# W603X.net
KiCad netlist of a schematic drawn in EAGLE
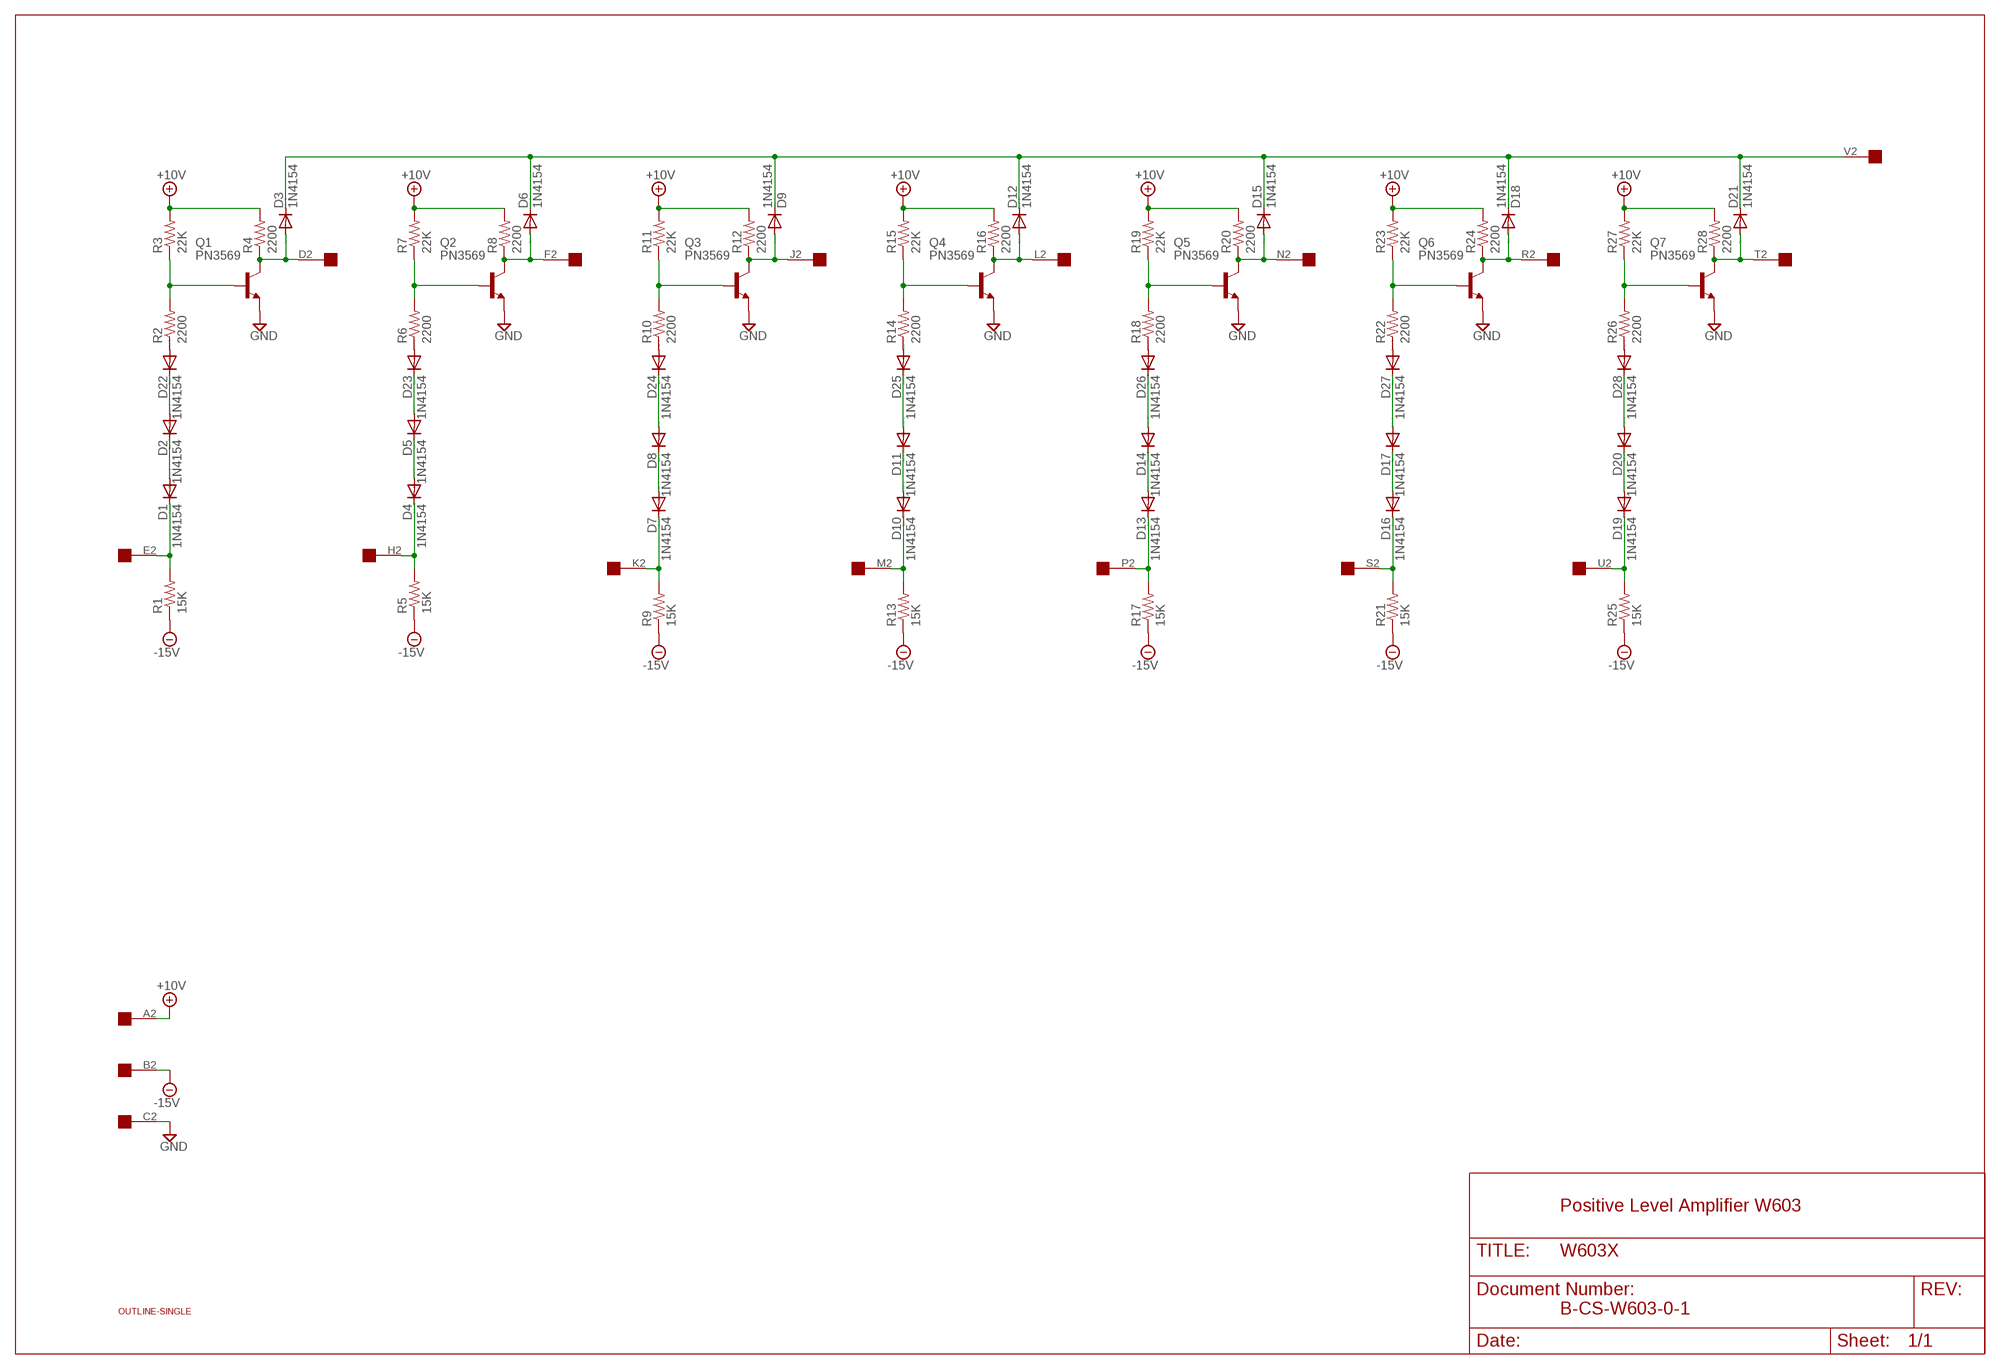
[diagram p0: schematic, sheet 1]

(export (version "E")
  (design (tool "Eeschema 10.0.6"))
  (components
    (comp (ref "D1")
      (value "1N4154")
      (footprint "eagle-import:DO35-10")
      (libsource (lib "eagle-import") (part "1N4148DO35-10"))
    )
    (comp (ref "D2")
      (value "1N4154")
      (footprint "eagle-import:DO35-10")
      (libsource (lib "eagle-import") (part "1N4148DO35-10"))
    )
    (comp (ref "D3")
      (value "1N4154")
      (footprint "eagle-import:DO35-10")
      (libsource (lib "eagle-import") (part "1N4148DO35-10"))
    )
    (comp (ref "D4")
      (value "1N4154")
      (footprint "eagle-import:DO35-10")
      (libsource (lib "eagle-import") (part "1N4148DO35-10"))
    )
    (comp (ref "D5")
      (value "1N4154")
      (footprint "eagle-import:DO35-10")
      (libsource (lib "eagle-import") (part "1N4148DO35-10"))
    )
    (comp (ref "D6")
      (value "1N4154")
      (footprint "eagle-import:DO35-10")
      (libsource (lib "eagle-import") (part "1N4148DO35-10"))
    )
    (comp (ref "D7")
      (value "1N4154")
      (footprint "eagle-import:DO35-10")
      (libsource (lib "eagle-import") (part "1N4148DO35-10"))
    )
    (comp (ref "D8")
      (value "1N4154")
      (footprint "eagle-import:DO35-10")
      (libsource (lib "eagle-import") (part "1N4148DO35-10"))
    )
    (comp (ref "D9")
      (value "1N4154")
      (footprint "eagle-import:DO35-10")
      (libsource (lib "eagle-import") (part "1N4148DO35-10"))
    )
    (comp (ref "D10")
      (value "1N4154")
      (footprint "eagle-import:DO35-10")
      (libsource (lib "eagle-import") (part "1N4148DO35-10"))
    )
    (comp (ref "D11")
      (value "1N4154")
      (footprint "eagle-import:DO35-10")
      (libsource (lib "eagle-import") (part "1N4148DO35-10"))
    )
    (comp (ref "D12")
      (value "1N4154")
      (footprint "eagle-import:DO35-10")
      (libsource (lib "eagle-import") (part "1N4148DO35-10"))
    )
    (comp (ref "D13")
      (value "1N4154")
      (footprint "eagle-import:DO35-10")
      (libsource (lib "eagle-import") (part "1N4148DO35-10"))
    )
    (comp (ref "D14")
      (value "1N4154")
      (footprint "eagle-import:DO35-10")
      (libsource (lib "eagle-import") (part "1N4148DO35-10"))
    )
    (comp (ref "D15")
      (value "1N4154")
      (footprint "eagle-import:DO35-10")
      (libsource (lib "eagle-import") (part "1N4148DO35-10"))
    )
    (comp (ref "D16")
      (value "1N4154")
      (footprint "eagle-import:DO35-10")
      (libsource (lib "eagle-import") (part "1N4148DO35-10"))
    )
    (comp (ref "D17")
      (value "1N4154")
      (footprint "eagle-import:DO35-10")
      (libsource (lib "eagle-import") (part "1N4148DO35-10"))
    )
    (comp (ref "D18")
      (value "1N4154")
      (footprint "eagle-import:DO35-10")
      (libsource (lib "eagle-import") (part "1N4148DO35-10"))
    )
    (comp (ref "D19")
      (value "1N4154")
      (footprint "eagle-import:DO35-10")
      (libsource (lib "eagle-import") (part "1N4148DO35-10"))
    )
    (comp (ref "D20")
      (value "1N4154")
      (footprint "eagle-import:DO35-10")
      (libsource (lib "eagle-import") (part "1N4148DO35-10"))
    )
    (comp (ref "D21")
      (value "1N4154")
      (footprint "eagle-import:DO35-10")
      (libsource (lib "eagle-import") (part "1N4148DO35-10"))
    )
    (comp (ref "D22")
      (value "1N4154")
      (footprint "eagle-import:DO35-10")
      (libsource (lib "eagle-import") (part "1N4148DO35-10"))
    )
    (comp (ref "D23")
      (value "1N4154")
      (footprint "eagle-import:DO35-10")
      (libsource (lib "eagle-import") (part "1N4148DO35-10"))
    )
    (comp (ref "D24")
      (value "1N4154")
      (footprint "eagle-import:DO35-10")
      (libsource (lib "eagle-import") (part "1N4148DO35-10"))
    )
    (comp (ref "D25")
      (value "1N4154")
      (footprint "eagle-import:DO35-10")
      (libsource (lib "eagle-import") (part "1N4148DO35-10"))
    )
    (comp (ref "D26")
      (value "1N4154")
      (footprint "eagle-import:DO35-10")
      (libsource (lib "eagle-import") (part "1N4148DO35-10"))
    )
    (comp (ref "D27")
      (value "1N4154")
      (footprint "eagle-import:DO35-10")
      (libsource (lib "eagle-import") (part "1N4148DO35-10"))
    )
    (comp (ref "D28")
      (value "1N4154")
      (footprint "eagle-import:DO35-10")
      (libsource (lib "eagle-import") (part "1N4148DO35-10"))
    )
    (comp (ref "Q1")
      (value "PN3569")
      (footprint "eagle-import:TO5")
      (libsource (lib "eagle-import") (part "2N2102"))
    )
    (comp (ref "Q2")
      (value "PN3569")
      (footprint "eagle-import:TO5")
      (libsource (lib "eagle-import") (part "2N2102"))
    )
    (comp (ref "Q3")
      (value "PN3569")
      (footprint "eagle-import:TO5")
      (libsource (lib "eagle-import") (part "2N2102"))
    )
    (comp (ref "Q4")
      (value "PN3569")
      (footprint "eagle-import:TO5")
      (libsource (lib "eagle-import") (part "2N2102"))
    )
    (comp (ref "Q5")
      (value "PN3569")
      (footprint "eagle-import:TO5")
      (libsource (lib "eagle-import") (part "2N2102"))
    )
    (comp (ref "Q6")
      (value "PN3569")
      (footprint "eagle-import:TO5")
      (libsource (lib "eagle-import") (part "2N2102"))
    )
    (comp (ref "Q7")
      (value "PN3569")
      (footprint "eagle-import:TO5")
      (libsource (lib "eagle-import") (part "2N2102"))
    )
    (comp (ref "R1")
      (value "15K")
      (footprint "eagle-import:0207_10")
      (libsource (lib "eagle-import") (part "R-US_0207/10"))
    )
    (comp (ref "R2")
      (value "2200")
      (footprint "eagle-import:0207_10")
      (libsource (lib "eagle-import") (part "R-US_0207/10"))
    )
    (comp (ref "R3")
      (value "22K")
      (footprint "eagle-import:0207_10")
      (libsource (lib "eagle-import") (part "R-US_0207/10"))
    )
    (comp (ref "R4")
      (value "2200")
      (footprint "eagle-import:0207_10")
      (libsource (lib "eagle-import") (part "R-US_0207/10"))
    )
    (comp (ref "R5")
      (value "15K")
      (footprint "eagle-import:0207_10")
      (libsource (lib "eagle-import") (part "R-US_0207/10"))
    )
    (comp (ref "R6")
      (value "2200")
      (footprint "eagle-import:0207_10")
      (libsource (lib "eagle-import") (part "R-US_0207/10"))
    )
    (comp (ref "R7")
      (value "22K")
      (footprint "eagle-import:0207_10")
      (libsource (lib "eagle-import") (part "R-US_0207/10"))
    )
    (comp (ref "R8")
      (value "2200")
      (footprint "eagle-import:0207_10")
      (libsource (lib "eagle-import") (part "R-US_0207/10"))
    )
    (comp (ref "R9")
      (value "15K")
      (footprint "eagle-import:0207_10")
      (libsource (lib "eagle-import") (part "R-US_0207/10"))
    )
    (comp (ref "R10")
      (value "2200")
      (footprint "eagle-import:0207_10")
      (libsource (lib "eagle-import") (part "R-US_0207/10"))
    )
    (comp (ref "R11")
      (value "22K")
      (footprint "eagle-import:0207_10")
      (libsource (lib "eagle-import") (part "R-US_0207/10"))
    )
    (comp (ref "R12")
      (value "2200")
      (footprint "eagle-import:0207_10")
      (libsource (lib "eagle-import") (part "R-US_0207/10"))
    )
    (comp (ref "R13")
      (value "15K")
      (footprint "eagle-import:0207_10")
      (libsource (lib "eagle-import") (part "R-US_0207/10"))
    )
    (comp (ref "R14")
      (value "2200")
      (footprint "eagle-import:0207_10")
      (libsource (lib "eagle-import") (part "R-US_0207/10"))
    )
    (comp (ref "R15")
      (value "22K")
      (footprint "eagle-import:0207_10")
      (libsource (lib "eagle-import") (part "R-US_0207/10"))
    )
    (comp (ref "R16")
      (value "2200")
      (footprint "eagle-import:0207_10")
      (libsource (lib "eagle-import") (part "R-US_0207/10"))
    )
    (comp (ref "R17")
      (value "15K")
      (footprint "eagle-import:0207_10")
      (libsource (lib "eagle-import") (part "R-US_0207/10"))
    )
    (comp (ref "R18")
      (value "2200")
      (footprint "eagle-import:0207_10")
      (libsource (lib "eagle-import") (part "R-US_0207/10"))
    )
    (comp (ref "R19")
      (value "22K")
      (footprint "eagle-import:0207_10")
      (libsource (lib "eagle-import") (part "R-US_0207/10"))
    )
    (comp (ref "R20")
      (value "2200")
      (footprint "eagle-import:0207_10")
      (libsource (lib "eagle-import") (part "R-US_0207/10"))
    )
    (comp (ref "R21")
      (value "15K")
      (footprint "eagle-import:0207_10")
      (libsource (lib "eagle-import") (part "R-US_0207/10"))
    )
    (comp (ref "R22")
      (value "2200")
      (footprint "eagle-import:0207_10")
      (libsource (lib "eagle-import") (part "R-US_0207/10"))
    )
    (comp (ref "R23")
      (value "22K")
      (footprint "eagle-import:0207_10")
      (libsource (lib "eagle-import") (part "R-US_0207/10"))
    )
    (comp (ref "R24")
      (value "2200")
      (footprint "eagle-import:0207_10")
      (libsource (lib "eagle-import") (part "R-US_0207/10"))
    )
    (comp (ref "R25")
      (value "15K")
      (footprint "eagle-import:0207_10")
      (libsource (lib "eagle-import") (part "R-US_0207/10"))
    )
    (comp (ref "R26")
      (value "2200")
      (footprint "eagle-import:0207_10")
      (libsource (lib "eagle-import") (part "R-US_0207/10"))
    )
    (comp (ref "R27")
      (value "22K")
      (footprint "eagle-import:0207_10")
      (libsource (lib "eagle-import") (part "R-US_0207/10"))
    )
    (comp (ref "R28")
      (value "2200")
      (footprint "eagle-import:0207_10")
      (libsource (lib "eagle-import") (part "R-US_0207/10"))
    )
    (comp (ref "U$1")
      (value "OUTLINE-SINGLE")
      (footprint "eagle-import:SINGLE")
      (libsource (lib "eagle-import") (part "OUTLINE-SINGLE"))
    )
    (comp (ref "U$2")
      (value "EDGE-1")
      (footprint "eagle-import:EDGE-CON1")
      (libsource (lib "eagle-import") (part "EDGE-1"))
    )
  )
  (nets
    (net (code "1") (name "+10V") (class "Default")
      (node (ref "R11") (pin "2") (pinfunction "2_2") (pintype "passive"))
      (node (ref "R12") (pin "2") (pinfunction "2_2") (pintype "passive"))
      (node (ref "R15") (pin "2") (pinfunction "2_2") (pintype "passive"))
      (node (ref "R16") (pin "2") (pinfunction "2_2") (pintype "passive"))
      (node (ref "R19") (pin "2") (pinfunction "2_2") (pintype "passive"))
      (node (ref "R20") (pin "2") (pinfunction "2_2") (pintype "passive"))
      (node (ref "R23") (pin "2") (pinfunction "2_2") (pintype "passive"))
      (node (ref "R24") (pin "2") (pinfunction "2_2") (pintype "passive"))
      (node (ref "R27") (pin "2") (pinfunction "2_2") (pintype "passive"))
      (node (ref "R28") (pin "2") (pinfunction "2_2") (pintype "passive"))
      (node (ref "R3") (pin "2") (pinfunction "2_2") (pintype "passive"))
      (node (ref "R4") (pin "2") (pinfunction "2_2") (pintype "passive"))
      (node (ref "R7") (pin "2") (pinfunction "2_2") (pintype "passive"))
      (node (ref "R8") (pin "2") (pinfunction "2_2") (pintype "passive"))
      (node (ref "U$2") (pin "A2") (pinfunction "1_A2") (pintype "bidirectional"))
    )
    (net (code "2") (name "-15V") (class "Default")
      (node (ref "R1") (pin "1") (pinfunction "1_1") (pintype "passive"))
      (node (ref "R13") (pin "1") (pinfunction "1_1") (pintype "passive"))
      (node (ref "R17") (pin "1") (pinfunction "1_1") (pintype "passive"))
      (node (ref "R21") (pin "1") (pinfunction "1_1") (pintype "passive"))
      (node (ref "R25") (pin "1") (pinfunction "1_1") (pintype "passive"))
      (node (ref "R5") (pin "1") (pinfunction "1_1") (pintype "passive"))
      (node (ref "R9") (pin "1") (pinfunction "1_1") (pintype "passive"))
      (node (ref "U$2") (pin "B2") (pinfunction "1_B2") (pintype "bidirectional"))
    )
    (net (code "3") (name "GND") (class "Default")
      (node (ref "Q1") (pin "1") (pinfunction "E_1") (pintype "passive"))
      (node (ref "Q2") (pin "1") (pinfunction "E_1") (pintype "passive"))
      (node (ref "Q3") (pin "1") (pinfunction "E_1") (pintype "passive"))
      (node (ref "Q4") (pin "1") (pinfunction "E_1") (pintype "passive"))
      (node (ref "Q5") (pin "1") (pinfunction "E_1") (pintype "passive"))
      (node (ref "Q6") (pin "1") (pinfunction "E_1") (pintype "passive"))
      (node (ref "Q7") (pin "1") (pinfunction "E_1") (pintype "passive"))
      (node (ref "U$2") (pin "C2") (pinfunction "1_C2") (pintype "bidirectional"))
    )
    (net (code "4") (name "Net-(D1-PadA)") (class "Default")
      (node (ref "D1") (pin "A") (pinfunction "A_A") (pintype "passive"))
      (node (ref "D2") (pin "C") (pinfunction "C_C") (pintype "passive"))
    )
    (net (code "5") (name "Net-(D2-PadA)") (class "Default")
      (node (ref "D2") (pin "A") (pinfunction "A_A") (pintype "passive"))
      (node (ref "D22") (pin "C") (pinfunction "C_C") (pintype "passive"))
    )
    (net (code "6") (name "Net-(D4-PadA)") (class "Default")
      (node (ref "D4") (pin "A") (pinfunction "A_A") (pintype "passive"))
      (node (ref "D5") (pin "C") (pinfunction "C_C") (pintype "passive"))
    )
    (net (code "7") (name "Net-(D7-PadA)") (class "Default")
      (node (ref "D7") (pin "A") (pinfunction "A_A") (pintype "passive"))
      (node (ref "D8") (pin "C") (pinfunction "C_C") (pintype "passive"))
    )
    (net (code "8") (name "Net-(D10-PadA)") (class "Default")
      (node (ref "D10") (pin "A") (pinfunction "A_A") (pintype "passive"))
      (node (ref "D11") (pin "C") (pinfunction "C_C") (pintype "passive"))
    )
    (net (code "9") (name "Net-(D11-PadA)") (class "Default")
      (node (ref "D11") (pin "A") (pinfunction "A_A") (pintype "passive"))
      (node (ref "D25") (pin "C") (pinfunction "C_C") (pintype "passive"))
    )
    (net (code "10") (name "Net-(D13-PadA)") (class "Default")
      (node (ref "D13") (pin "A") (pinfunction "A_A") (pintype "passive"))
      (node (ref "D14") (pin "C") (pinfunction "C_C") (pintype "passive"))
    )
    (net (code "11") (name "Net-(D14-PadA)") (class "Default")
      (node (ref "D14") (pin "A") (pinfunction "A_A") (pintype "passive"))
      (node (ref "D26") (pin "C") (pinfunction "C_C") (pintype "passive"))
    )
    (net (code "12") (name "Net-(D16-PadA)") (class "Default")
      (node (ref "D16") (pin "A") (pinfunction "A_A") (pintype "passive"))
      (node (ref "D17") (pin "C") (pinfunction "C_C") (pintype "passive"))
    )
    (net (code "13") (name "Net-(D17-PadA)") (class "Default")
      (node (ref "D17") (pin "A") (pinfunction "A_A") (pintype "passive"))
      (node (ref "D27") (pin "C") (pinfunction "C_C") (pintype "passive"))
    )
    (net (code "14") (name "Net-(D19-PadA)") (class "Default")
      (node (ref "D19") (pin "A") (pinfunction "A_A") (pintype "passive"))
      (node (ref "D20") (pin "C") (pinfunction "C_C") (pintype "passive"))
    )
    (net (code "15") (name "Net-(D20-PadA)") (class "Default")
      (node (ref "D20") (pin "A") (pinfunction "A_A") (pintype "passive"))
      (node (ref "D28") (pin "C") (pinfunction "C_C") (pintype "passive"))
    )
    (net (code "16") (name "Net-(D22-PadA)") (class "Default")
      (node (ref "D22") (pin "A") (pinfunction "A_A") (pintype "passive"))
      (node (ref "R2") (pin "1") (pinfunction "1_1") (pintype "passive"))
    )
    (net (code "17") (name "Net-(D23-PadA)") (class "Default")
      (node (ref "D23") (pin "A") (pinfunction "A_A") (pintype "passive"))
      (node (ref "R6") (pin "1") (pinfunction "1_1") (pintype "passive"))
    )
    (net (code "18") (name "Net-(D23-PadC)") (class "Default")
      (node (ref "D23") (pin "C") (pinfunction "C_C") (pintype "passive"))
      (node (ref "D5") (pin "A") (pinfunction "A_A") (pintype "passive"))
    )
    (net (code "19") (name "Net-(D24-PadA)") (class "Default")
      (node (ref "D24") (pin "A") (pinfunction "A_A") (pintype "passive"))
      (node (ref "R10") (pin "1") (pinfunction "1_1") (pintype "passive"))
    )
    (net (code "20") (name "Net-(D24-PadC)") (class "Default")
      (node (ref "D24") (pin "C") (pinfunction "C_C") (pintype "passive"))
      (node (ref "D8") (pin "A") (pinfunction "A_A") (pintype "passive"))
    )
    (net (code "21") (name "Net-(D25-PadA)") (class "Default")
      (node (ref "D25") (pin "A") (pinfunction "A_A") (pintype "passive"))
      (node (ref "R14") (pin "1") (pinfunction "1_1") (pintype "passive"))
    )
    (net (code "22") (name "Net-(D26-PadA)") (class "Default")
      (node (ref "D26") (pin "A") (pinfunction "A_A") (pintype "passive"))
      (node (ref "R18") (pin "1") (pinfunction "1_1") (pintype "passive"))
    )
    (net (code "23") (name "Net-(D27-PadA)") (class "Default")
      (node (ref "D27") (pin "A") (pinfunction "A_A") (pintype "passive"))
      (node (ref "R22") (pin "1") (pinfunction "1_1") (pintype "passive"))
    )
    (net (code "24") (name "Net-(D28-PadA)") (class "Default")
      (node (ref "D28") (pin "A") (pinfunction "A_A") (pintype "passive"))
      (node (ref "R26") (pin "1") (pinfunction "1_1") (pintype "passive"))
    )
    (net (code "25") (name "Net-(Q1-B)") (class "Default")
      (node (ref "Q1") (pin "2") (pinfunction "B_2") (pintype "passive"))
      (node (ref "R2") (pin "2") (pinfunction "2_2") (pintype "passive"))
      (node (ref "R3") (pin "1") (pinfunction "1_1") (pintype "passive"))
    )
    (net (code "26") (name "Net-(Q1-C)") (class "Default")
      (node (ref "D3") (pin "A") (pinfunction "A_A") (pintype "passive"))
      (node (ref "Q1") (pin "3") (pinfunction "C_3") (pintype "passive"))
      (node (ref "R4") (pin "1") (pinfunction "1_1") (pintype "passive"))
      (node (ref "U$2") (pin "D2") (pinfunction "1_D2") (pintype "bidirectional"))
    )
    (net (code "27") (name "Net-(Q2-B)") (class "Default")
      (node (ref "Q2") (pin "2") (pinfunction "B_2") (pintype "passive"))
      (node (ref "R6") (pin "2") (pinfunction "2_2") (pintype "passive"))
      (node (ref "R7") (pin "1") (pinfunction "1_1") (pintype "passive"))
    )
    (net (code "28") (name "Net-(Q2-C)") (class "Default")
      (node (ref "D6") (pin "A") (pinfunction "A_A") (pintype "passive"))
      (node (ref "Q2") (pin "3") (pinfunction "C_3") (pintype "passive"))
      (node (ref "R8") (pin "1") (pinfunction "1_1") (pintype "passive"))
      (node (ref "U$2") (pin "F2") (pinfunction "1_F2") (pintype "bidirectional"))
    )
    (net (code "29") (name "Net-(Q3-B)") (class "Default")
      (node (ref "Q3") (pin "2") (pinfunction "B_2") (pintype "passive"))
      (node (ref "R10") (pin "2") (pinfunction "2_2") (pintype "passive"))
      (node (ref "R11") (pin "1") (pinfunction "1_1") (pintype "passive"))
    )
    (net (code "30") (name "Net-(Q3-C)") (class "Default")
      (node (ref "D9") (pin "A") (pinfunction "A_A") (pintype "passive"))
      (node (ref "Q3") (pin "3") (pinfunction "C_3") (pintype "passive"))
      (node (ref "R12") (pin "1") (pinfunction "1_1") (pintype "passive"))
      (node (ref "U$2") (pin "J2") (pinfunction "1_J2") (pintype "bidirectional"))
    )
    (net (code "31") (name "Net-(Q4-B)") (class "Default")
      (node (ref "Q4") (pin "2") (pinfunction "B_2") (pintype "passive"))
      (node (ref "R14") (pin "2") (pinfunction "2_2") (pintype "passive"))
      (node (ref "R15") (pin "1") (pinfunction "1_1") (pintype "passive"))
    )
    (net (code "32") (name "Net-(Q4-C)") (class "Default")
      (node (ref "D12") (pin "A") (pinfunction "A_A") (pintype "passive"))
      (node (ref "Q4") (pin "3") (pinfunction "C_3") (pintype "passive"))
      (node (ref "R16") (pin "1") (pinfunction "1_1") (pintype "passive"))
      (node (ref "U$2") (pin "L2") (pinfunction "1_L2") (pintype "bidirectional"))
    )
    (net (code "33") (name "Net-(Q5-B)") (class "Default")
      (node (ref "Q5") (pin "2") (pinfunction "B_2") (pintype "passive"))
      (node (ref "R18") (pin "2") (pinfunction "2_2") (pintype "passive"))
      (node (ref "R19") (pin "1") (pinfunction "1_1") (pintype "passive"))
    )
    (net (code "34") (name "Net-(Q5-C)") (class "Default")
      (node (ref "D15") (pin "A") (pinfunction "A_A") (pintype "passive"))
      (node (ref "Q5") (pin "3") (pinfunction "C_3") (pintype "passive"))
      (node (ref "R20") (pin "1") (pinfunction "1_1") (pintype "passive"))
      (node (ref "U$2") (pin "N2") (pinfunction "1_N2") (pintype "bidirectional"))
    )
    (net (code "35") (name "Net-(Q6-B)") (class "Default")
      (node (ref "Q6") (pin "2") (pinfunction "B_2") (pintype "passive"))
      (node (ref "R22") (pin "2") (pinfunction "2_2") (pintype "passive"))
      (node (ref "R23") (pin "1") (pinfunction "1_1") (pintype "passive"))
    )
    (net (code "36") (name "Net-(Q6-C)") (class "Default")
      (node (ref "D18") (pin "A") (pinfunction "A_A") (pintype "passive"))
      (node (ref "Q6") (pin "3") (pinfunction "C_3") (pintype "passive"))
      (node (ref "R24") (pin "1") (pinfunction "1_1") (pintype "passive"))
      (node (ref "U$2") (pin "R2") (pinfunction "1_R2") (pintype "bidirectional"))
    )
    (net (code "37") (name "Net-(Q7-B)") (class "Default")
      (node (ref "Q7") (pin "2") (pinfunction "B_2") (pintype "passive"))
      (node (ref "R26") (pin "2") (pinfunction "2_2") (pintype "passive"))
      (node (ref "R27") (pin "1") (pinfunction "1_1") (pintype "passive"))
    )
    (net (code "38") (name "Net-(Q7-C)") (class "Default")
      (node (ref "D21") (pin "A") (pinfunction "A_A") (pintype "passive"))
      (node (ref "Q7") (pin "3") (pinfunction "C_3") (pintype "passive"))
      (node (ref "R28") (pin "1") (pinfunction "1_1") (pintype "passive"))
      (node (ref "U$2") (pin "T2") (pinfunction "1_T2") (pintype "bidirectional"))
    )
    (net (code "39") (name "Net-(U$2E-1)") (class "Default")
      (node (ref "D1") (pin "C") (pinfunction "C_C") (pintype "passive"))
      (node (ref "R1") (pin "2") (pinfunction "2_2") (pintype "passive"))
      (node (ref "U$2") (pin "E2") (pinfunction "1_E2") (pintype "bidirectional"))
    )
    (net (code "40") (name "Net-(U$2G-1)") (class "Default")
      (node (ref "D4") (pin "C") (pinfunction "C_C") (pintype "passive"))
      (node (ref "R5") (pin "2") (pinfunction "2_2") (pintype "passive"))
      (node (ref "U$2") (pin "H2") (pinfunction "1_H2") (pintype "bidirectional"))
    )
    (net (code "41") (name "Net-(U$2I-1)") (class "Default")
      (node (ref "D7") (pin "C") (pinfunction "C_C") (pintype "passive"))
      (node (ref "R9") (pin "2") (pinfunction "2_2") (pintype "passive"))
      (node (ref "U$2") (pin "K2") (pinfunction "1_K2") (pintype "bidirectional"))
    )
    (net (code "42") (name "Net-(U$2K-1)") (class "Default")
      (node (ref "D10") (pin "C") (pinfunction "C_C") (pintype "passive"))
      (node (ref "R13") (pin "2") (pinfunction "2_2") (pintype "passive"))
      (node (ref "U$2") (pin "M2") (pinfunction "1_M2") (pintype "bidirectional"))
    )
    (net (code "43") (name "Net-(U$2M-1)") (class "Default")
      (node (ref "D13") (pin "C") (pinfunction "C_C") (pintype "passive"))
      (node (ref "R17") (pin "2") (pinfunction "2_2") (pintype "passive"))
      (node (ref "U$2") (pin "P2") (pinfunction "1_P2") (pintype "bidirectional"))
    )
    (net (code "44") (name "Net-(U$2O-1)") (class "Default")
      (node (ref "D16") (pin "C") (pinfunction "C_C") (pintype "passive"))
      (node (ref "R21") (pin "2") (pinfunction "2_2") (pintype "passive"))
      (node (ref "U$2") (pin "S2") (pinfunction "1_S2") (pintype "bidirectional"))
    )
    (net (code "45") (name "Net-(U$2Q-1)") (class "Default")
      (node (ref "D19") (pin "C") (pinfunction "C_C") (pintype "passive"))
      (node (ref "R25") (pin "2") (pinfunction "2_2") (pintype "passive"))
      (node (ref "U$2") (pin "U2") (pinfunction "1_U2") (pintype "bidirectional"))
    )
    (net (code "46") (name "Net-(U$2R-1)") (class "Default")
      (node (ref "D12") (pin "C") (pinfunction "C_C") (pintype "passive"))
      (node (ref "D15") (pin "C") (pinfunction "C_C") (pintype "passive"))
      (node (ref "D18") (pin "C") (pinfunction "C_C") (pintype "passive"))
      (node (ref "D21") (pin "C") (pinfunction "C_C") (pintype "passive"))
      (node (ref "D3") (pin "C") (pinfunction "C_C") (pintype "passive"))
      (node (ref "D6") (pin "C") (pinfunction "C_C") (pintype "passive"))
      (node (ref "D9") (pin "C") (pinfunction "C_C") (pintype "passive"))
      (node (ref "U$2") (pin "V2") (pinfunction "1_V2") (pintype "bidirectional"))
    )
  )
)
